# ir2104_V1_0.net
KiCad netlist of a schematic drawn in EasyEDA Pro
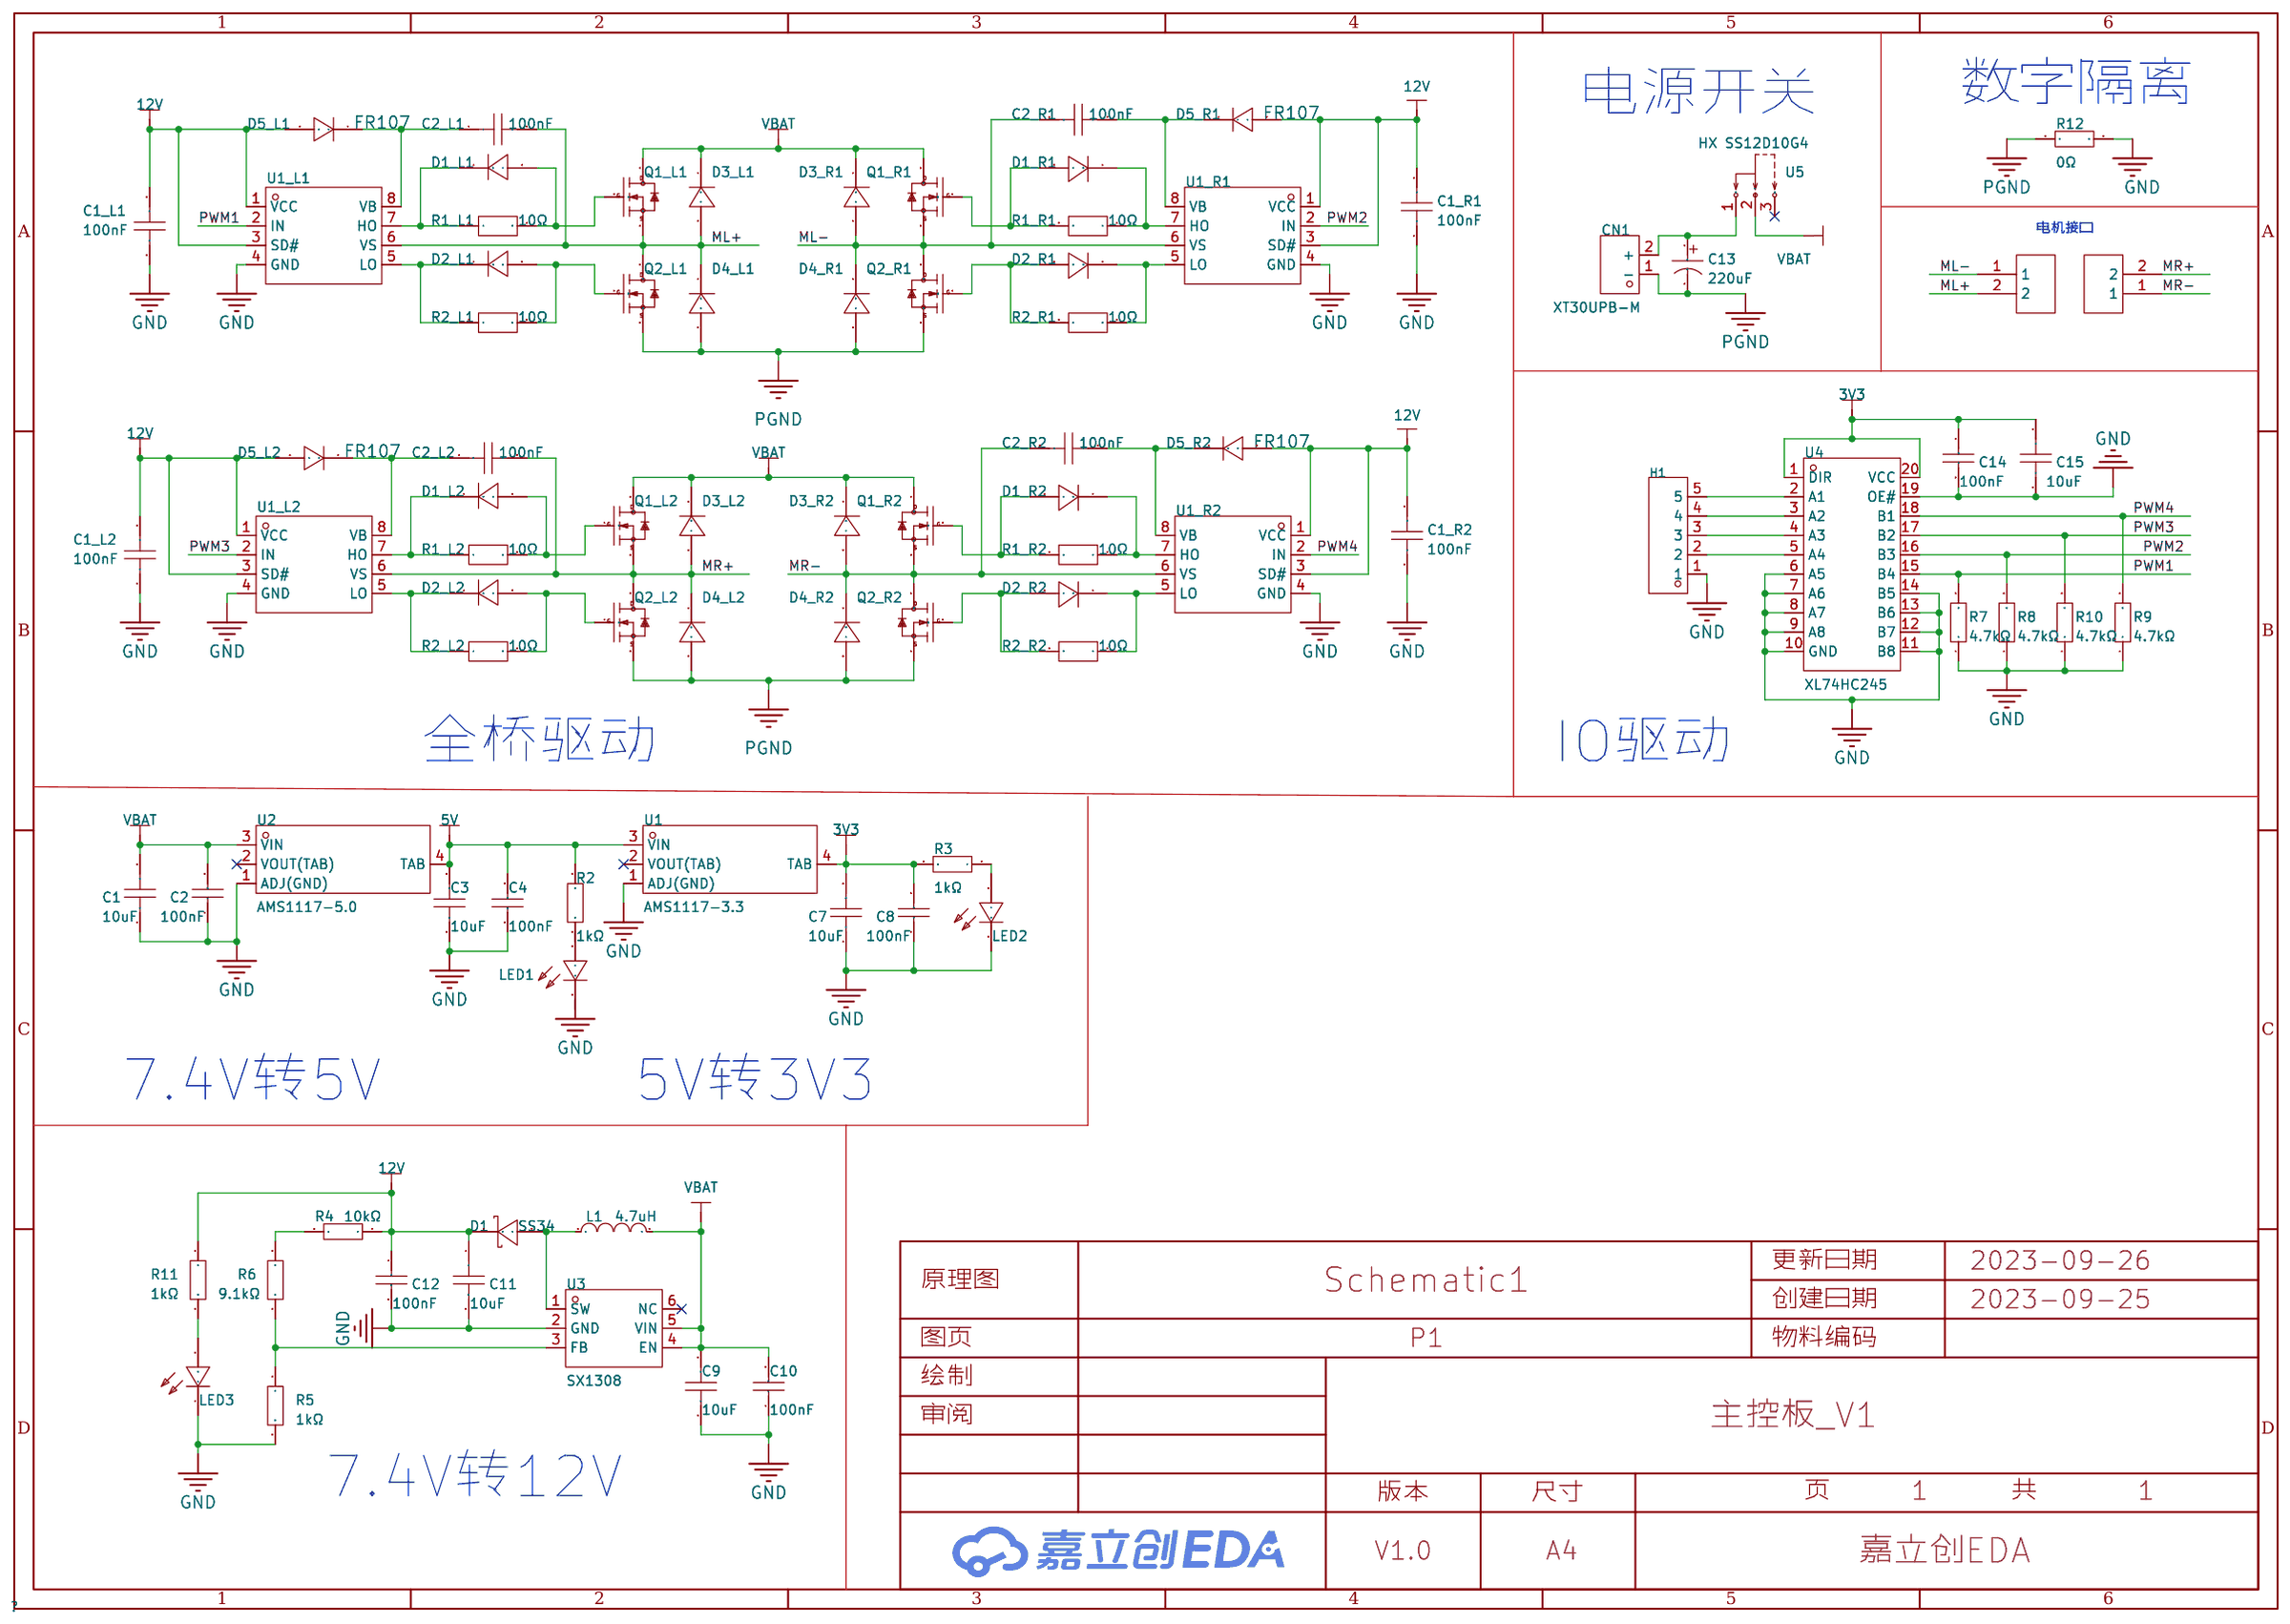
[diagram p0: schematic sheet]

(export (version "E")
  (design (tool "Eeschema 10.0.6"))
  (components
    (comp (ref "C1")
      (value "10uF")
      (footprint "easyedapro:C0603")
      (description "容值:10uF;精度:±20%;额定电压:25V;材质(温度系数):X5R;")
      (fields
        (field (name "Manufacturer Part") "CL10A106MA8NRNC")
        (field (name "Manufacturer") "SAMSUNG(三星)")
      )
      (libsource (lib "easyedapro") (part "CL10A106MA8NRNC"))
    )
    (comp (ref "C1_L1")
      (value "100nF")
      (footprint "easyedapro:C0603")
      (description "容值:100nF;精度:±10%;额定电压:50V;材质(温度系数):X7R;")
      (fields
        (field (name "Manufacturer Part") "CL10B104KB8NNNC")
        (field (name "Manufacturer") "SAMSUNG(三星)")
      )
      (libsource (lib "easyedapro") (part "CL10B104KB8NNNC"))
    )
    (comp (ref "C1_L2")
      (value "100nF")
      (footprint "easyedapro:C0603")
      (description "容值:100nF;精度:±10%;额定电压:50V;材质(温度系数):X7R;")
      (fields
        (field (name "Manufacturer Part") "CL10B104KB8NNNC")
        (field (name "Manufacturer") "SAMSUNG(三星)")
      )
      (libsource (lib "easyedapro") (part "CL10B104KB8NNNC"))
    )
    (comp (ref "C1_R1")
      (value "100nF")
      (footprint "easyedapro:C0603")
      (description "容值:100nF;精度:±10%;额定电压:50V;材质(温度系数):X7R;")
      (fields
        (field (name "Manufacturer Part") "CL10B104KB8NNNC")
        (field (name "Manufacturer") "SAMSUNG(三星)")
      )
      (libsource (lib "easyedapro") (part "CL10B104KB8NNNC"))
    )
    (comp (ref "C1_R2")
      (value "100nF")
      (footprint "easyedapro:C0603")
      (description "容值:100nF;精度:±10%;额定电压:50V;材质(温度系数):X7R;")
      (fields
        (field (name "Manufacturer Part") "CL10B104KB8NNNC")
        (field (name "Manufacturer") "SAMSUNG(三星)")
      )
      (libsource (lib "easyedapro") (part "CL10B104KB8NNNC"))
    )
    (comp (ref "C2")
      (value "100nF")
      (footprint "easyedapro:C0603")
      (description "容值:100nF;精度:±10%;额定电压:50V;材质(温度系数):X7R;")
      (fields (field (name "Manufacturer Part") "0603B104K500NT") (field (name "Manufacturer") "FH(风华)"))
      (libsource (lib "easyedapro") (part "0603B104K500NT"))
    )
    (comp (ref "C2_L1")
      (value "100nF")
      (footprint "easyedapro:C0603")
      (description "容值:100nF;精度:±10%;额定电压:50V;材质(温度系数):X7R;")
      (fields
        (field (name "Manufacturer Part") "CL10B104KB8NNNC")
        (field (name "Manufacturer") "SAMSUNG(三星)")
      )
      (libsource (lib "easyedapro") (part "CL10B104KB8NNNC"))
    )
    (comp (ref "C2_L2")
      (value "100nF")
      (footprint "easyedapro:C0603")
      (description "容值:100nF;精度:±10%;额定电压:50V;材质(温度系数):X7R;")
      (fields
        (field (name "Manufacturer Part") "CL10B104KB8NNNC")
        (field (name "Manufacturer") "SAMSUNG(三星)")
      )
      (libsource (lib "easyedapro") (part "CL10B104KB8NNNC"))
    )
    (comp (ref "C2_R1")
      (value "100nF")
      (footprint "easyedapro:C0603")
      (description "容值:100nF;精度:±10%;额定电压:50V;材质(温度系数):X7R;")
      (fields
        (field (name "Manufacturer Part") "CL10B104KB8NNNC")
        (field (name "Manufacturer") "SAMSUNG(三星)")
      )
      (libsource (lib "easyedapro") (part "CL10B104KB8NNNC"))
    )
    (comp (ref "C2_R2")
      (value "100nF")
      (footprint "easyedapro:C0603")
      (description "容值:100nF;精度:±10%;额定电压:50V;材质(温度系数):X7R;")
      (fields
        (field (name "Manufacturer Part") "CL10B104KB8NNNC")
        (field (name "Manufacturer") "SAMSUNG(三星)")
      )
      (libsource (lib "easyedapro") (part "CL10B104KB8NNNC"))
    )
    (comp (ref "C3")
      (value "10uF")
      (footprint "easyedapro:C0603")
      (description "容值:10uF;精度:±20%;额定电压:25V;材质(温度系数):X5R;")
      (fields
        (field (name "Manufacturer Part") "CL10A106MA8NRNC")
        (field (name "Manufacturer") "SAMSUNG(三星)")
      )
      (libsource (lib "easyedapro") (part "CL10A106MA8NRNC"))
    )
    (comp (ref "C4")
      (value "100nF")
      (footprint "easyedapro:C0603")
      (description "容值:100nF;精度:±10%;额定电压:50V;材质(温度系数):X7R;")
      (fields (field (name "Manufacturer Part") "0603B104K500NT") (field (name "Manufacturer") "FH(风华)"))
      (libsource (lib "easyedapro") (part "0603B104K500NT"))
    )
    (comp (ref "C7")
      (value "10uF")
      (footprint "easyedapro:C0603")
      (description "容值:10uF;精度:±20%;额定电压:25V;材质(温度系数):X5R;")
      (fields
        (field (name "Manufacturer Part") "CL10A106MA8NRNC")
        (field (name "Manufacturer") "SAMSUNG(三星)")
      )
      (libsource (lib "easyedapro") (part "CL10A106MA8NRNC"))
    )
    (comp (ref "C8")
      (value "100nF")
      (footprint "easyedapro:C0603")
      (description "容值:100nF;精度:±10%;额定电压:50V;材质(温度系数):X7R;")
      (fields (field (name "Manufacturer Part") "0603B104K500NT") (field (name "Manufacturer") "FH(风华)"))
      (libsource (lib "easyedapro") (part "0603B104K500NT"))
    )
    (comp (ref "C9")
      (value "10uF")
      (footprint "easyedapro:C0603")
      (description "容值:10uF;精度:±20%;额定电压:25V;材质(温度系数):X5R;")
      (fields
        (field (name "Manufacturer Part") "CL10A106MA8NRNC")
        (field (name "Manufacturer") "SAMSUNG(三星)")
      )
      (libsource (lib "easyedapro") (part "CL10A106MA8NRNC"))
    )
    (comp (ref "C10")
      (value "100nF")
      (footprint "easyedapro:C0603")
      (description "容值:100nF;精度:±10%;额定电压:50V;材质(温度系数):X7R;")
      (fields (field (name "Manufacturer Part") "0603B104K500NT") (field (name "Manufacturer") "FH(风华)"))
      (libsource (lib "easyedapro") (part "0603B104K500NT"))
    )
    (comp (ref "C11")
      (value "10uF")
      (footprint "easyedapro:C0603")
      (description "容值:10uF;精度:±20%;额定电压:25V;材质(温度系数):X5R;")
      (fields
        (field (name "Manufacturer Part") "CL10A106MA8NRNC")
        (field (name "Manufacturer") "SAMSUNG(三星)")
      )
      (libsource (lib "easyedapro") (part "CL10A106MA8NRNC"))
    )
    (comp (ref "C12")
      (value "100nF")
      (footprint "easyedapro:C0603")
      (description "容值:100nF;精度:±10%;额定电压:50V;材质(温度系数):X7R;")
      (fields (field (name "Manufacturer Part") "0603B104K500NT") (field (name "Manufacturer") "FH(风华)"))
      (libsource (lib "easyedapro") (part "0603B104K500NT"))
    )
    (comp (ref "C13")
      (value "220uF")
      (footprint "easyedapro:CAP-TH_BD8.0-P3.50-D0.6-FD")
      (description "容值:220uF;精度:±20%;额定电压:35V;纹波电流:-;等效串联电阻:-;")
      (fields
        (field (name "Manufacturer Part") "KM227M035F12RR0VH2FP0")
        (field (name "Manufacturer") "CX(承兴)")
      )
      (libsource (lib "easyedapro") (part "220uf/35V"))
    )
    (comp (ref "C14")
      (value "100nF")
      (footprint "easyedapro:C0603")
      (description "容值:100nF;精度:±10%;额定电压:50V;材质(温度系数):X7R;")
      (fields (field (name "Manufacturer Part") "0603B104K500NT") (field (name "Manufacturer") "FH(风华)"))
      (libsource (lib "easyedapro") (part "0603B104K500NT"))
    )
    (comp (ref "C15")
      (value "10uF")
      (footprint "easyedapro:C0603")
      (description "容值:10uF;精度:±20%;额定电压:25V;材质(温度系数):X5R;")
      (fields
        (field (name "Manufacturer Part") "CL10A106MA8NRNC")
        (field (name "Manufacturer") "SAMSUNG(三星)")
      )
      (libsource (lib "easyedapro") (part "CL10A106MA8NRNC"))
    )
    (comp (ref "CN1")
      (value "XT30UPB-M")
      (footprint "easyedapro:CONN-TH_XT30UPB-M")
      (fields (field (name "Manufacturer") "AMASS(艾迈斯)"))
      (libsource (lib "easyedapro") (part "XT30UPB-M"))
    )
    (comp (ref "D1")
      (value "SS34")
      (footprint "easyedapro:SMA_L4.3-W2.6-LS5.2-RD")
      (description "二极管配置:独立式;直流反向耐压(Vr):40V;平均整流电流(Io):3A;正向压降(Vf):550mV@3A;")
      (fields (field (name "Manufacturer") "MDD"))
      (libsource (lib "easyedapro") (part "SS34_C8678"))
    )
    (comp (ref "D1_L1")
      (value "US1M")
      (footprint "easyedapro:SMA_L4.4-W2.8-LS5.4-RD")
      (fields (field (name "Manufacturer") "MDD"))
      (libsource (lib "easyedapro") (part "US1MG_C412437"))
    )
    (comp (ref "D1_L2")
      (value "US1M")
      (footprint "easyedapro:SMA_L4.4-W2.8-LS5.4-RD")
      (fields (field (name "Manufacturer") "MDD"))
      (libsource (lib "easyedapro") (part "US1MG_C412437"))
    )
    (comp (ref "D1_R1")
      (value "US1M")
      (footprint "easyedapro:SMA_L4.4-W2.8-LS5.4-RD")
      (fields (field (name "Manufacturer") "MDD"))
      (libsource (lib "easyedapro") (part "US1MG_C412437"))
    )
    (comp (ref "D1_R2")
      (value "US1M")
      (footprint "easyedapro:SMA_L4.4-W2.8-LS5.4-RD")
      (fields (field (name "Manufacturer") "MDD"))
      (libsource (lib "easyedapro") (part "US1MG_C412437"))
    )
    (comp (ref "D2_L1")
      (value "US1M")
      (footprint "easyedapro:SMA_L4.4-W2.8-LS5.4-RD")
      (fields (field (name "Manufacturer") "MDD"))
      (libsource (lib "easyedapro") (part "US1MG_C412437"))
    )
    (comp (ref "D2_L2")
      (value "US1M")
      (footprint "easyedapro:SMA_L4.4-W2.8-LS5.4-RD")
      (fields (field (name "Manufacturer") "MDD"))
      (libsource (lib "easyedapro") (part "US1MG_C412437"))
    )
    (comp (ref "D2_R1")
      (value "US1M")
      (footprint "easyedapro:SMA_L4.4-W2.8-LS5.4-RD")
      (fields (field (name "Manufacturer") "MDD"))
      (libsource (lib "easyedapro") (part "US1MG_C412437"))
    )
    (comp (ref "D2_R2")
      (value "US1M")
      (footprint "easyedapro:SMA_L4.4-W2.8-LS5.4-RD")
      (fields (field (name "Manufacturer") "MDD"))
      (libsource (lib "easyedapro") (part "US1MG_C412437"))
    )
    (comp (ref "D3_L1")
      (value "US1M")
      (footprint "easyedapro:SMA_L4.4-W2.8-LS5.4-RD")
      (fields (field (name "Manufacturer") "MDD"))
      (libsource (lib "easyedapro") (part "US1MG_C412437"))
    )
    (comp (ref "D3_L2")
      (value "US1M")
      (footprint "easyedapro:SMA_L4.4-W2.8-LS5.4-RD")
      (fields (field (name "Manufacturer") "MDD"))
      (libsource (lib "easyedapro") (part "US1MG_C412437"))
    )
    (comp (ref "D3_R1")
      (value "US1M")
      (footprint "easyedapro:SMA_L4.4-W2.8-LS5.4-RD")
      (fields (field (name "Manufacturer") "MDD"))
      (libsource (lib "easyedapro") (part "US1MG_C412437"))
    )
    (comp (ref "D3_R2")
      (value "US1M")
      (footprint "easyedapro:SMA_L4.4-W2.8-LS5.4-RD")
      (fields (field (name "Manufacturer") "MDD"))
      (libsource (lib "easyedapro") (part "US1MG_C412437"))
    )
    (comp (ref "D4_L1")
      (value "US1M")
      (footprint "easyedapro:SMA_L4.4-W2.8-LS5.4-RD")
      (fields (field (name "Manufacturer") "MDD"))
      (libsource (lib "easyedapro") (part "US1MG_C412437"))
    )
    (comp (ref "D4_L2")
      (value "US1M")
      (footprint "easyedapro:SMA_L4.4-W2.8-LS5.4-RD")
      (fields (field (name "Manufacturer") "MDD"))
      (libsource (lib "easyedapro") (part "US1MG_C412437"))
    )
    (comp (ref "D4_R1")
      (value "US1M")
      (footprint "easyedapro:SMA_L4.4-W2.8-LS5.4-RD")
      (fields (field (name "Manufacturer") "MDD"))
      (libsource (lib "easyedapro") (part "US1MG_C412437"))
    )
    (comp (ref "D4_R2")
      (value "US1M")
      (footprint "easyedapro:SMA_L4.4-W2.8-LS5.4-RD")
      (fields (field (name "Manufacturer") "MDD"))
      (libsource (lib "easyedapro") (part "US1MG_C412437"))
    )
    (comp (ref "D5_L1")
      (value "FR107")
      (footprint "easyedapro:SOD-123_L2.8-W1.8-LS3.7-RD")
      (fields (field (name "Manufacturer") "BORN(伯恩半导体)"))
      (libsource (lib "easyedapro") (part "FR107_C511885"))
    )
    (comp (ref "D5_L2")
      (value "FR107")
      (footprint "easyedapro:SOD-123_L2.8-W1.8-LS3.7-RD")
      (fields (field (name "Manufacturer") "BORN(伯恩半导体)"))
      (libsource (lib "easyedapro") (part "FR107_C511885"))
    )
    (comp (ref "D5_R1")
      (value "FR107")
      (footprint "easyedapro:SOD-123_L2.8-W1.8-LS3.7-RD")
      (fields (field (name "Manufacturer") "BORN(伯恩半导体)"))
      (libsource (lib "easyedapro") (part "FR107_C511885"))
    )
    (comp (ref "D5_R2")
      (value "FR107")
      (footprint "easyedapro:SOD-123_L2.8-W1.8-LS3.7-RD")
      (fields (field (name "Manufacturer") "BORN(伯恩半导体)"))
      (libsource (lib "easyedapro") (part "FR107_C511885"))
    )
    (comp (ref "H1")
      (value "PZ254V-11-05P")
      (footprint "easyedapro:HDR-TH_5P-P2.54-V-M")
      (fields (field (name "Manufacturer") "XFCN(兴飞)"))
      (libsource (lib "easyedapro") (part "PZ254V-11-05P"))
    )
    (comp (ref "L1")
      (value "4.7uH")
      (footprint "easyedapro:IND-SMD_L5.4-W5.2_FXL0530")
      (description "电感值:4.7uH;精度:±20%;额定电流:4.5A;饱和电流(Isat):5A;")
      (fields (field (name "Manufacturer Part") "FXL0530-4R7-M") (field (name "Manufacturer") "cjiang(长江微电)"))
      (libsource (lib "easyedapro") (part "FXL0530-4R7-M"))
    )
    (comp (ref "LED1")
      (value "NCD0603R1")
      (footprint "easyedapro:LED0603-RD_RED")
      (description "发光颜色:红灯;")
      (fields (field (name "Manufacturer") "国星光电"))
      (libsource (lib "easyedapro") (part "FC-DA1608HRK-620D"))
    )
    (comp (ref "LED2")
      (value "NCD0603R1")
      (footprint "easyedapro:LED0603-RD_RED")
      (description "发光颜色:红灯;")
      (fields (field (name "Manufacturer") "国星光电"))
      (libsource (lib "easyedapro") (part "FC-DA1608HRK-620D"))
    )
    (comp (ref "LED3")
      (value "NCD0603R1")
      (footprint "easyedapro:LED0603-RD_RED")
      (description "发光颜色:红灯;")
      (fields (field (name "Manufacturer") "国星光电"))
      (libsource (lib "easyedapro") (part "FC-DA1608HRK-620D"))
    )
    (comp (ref "P1")
      (value "WJ500V-5.08-2P")
      (footprint "easyedapro:CONN-TH_2P-P5.00_WJ500V-5.08-2P")
      (fields (field (name "Manufacturer") "KANGNEX(康奈克斯电气)"))
      (libsource (lib "easyedapro") (part "WJ500V-5.08-2P-14-00A"))
    )
    (comp (ref "P2")
      (value "WJ500V-5.08-2P")
      (footprint "easyedapro:CONN-TH_2P-P5.00_WJ500V-5.08-2P")
      (fields (field (name "Manufacturer") "KANGNEX(康奈克斯电气)"))
      (libsource (lib "easyedapro") (part "WJ500V-5.08-2P-14-00A"))
    )
    (comp (ref "Q1_L1")
      (value "IRFR3607TRPBF")
      (footprint "easyedapro:TO-252-3_L6.5-W5.8-P4.58-BL")
      (fields (field (name "Manufacturer") "Infineon(英飞凌)"))
      (libsource (lib "easyedapro") (part "IRFR3607TRPBF"))
    )
    (comp (ref "Q1_L2")
      (value "IRFR3607TRPBF")
      (footprint "easyedapro:TO-252-3_L6.5-W5.8-P4.58-BL")
      (fields (field (name "Manufacturer") "Infineon(英飞凌)"))
      (libsource (lib "easyedapro") (part "IRFR3607TRPBF"))
    )
    (comp (ref "Q1_R1")
      (value "IRFR3607TRPBF")
      (footprint "easyedapro:TO-252-3_L6.5-W5.8-P4.58-BL")
      (fields (field (name "Manufacturer") "Infineon(英飞凌)"))
      (libsource (lib "easyedapro") (part "IRFR3607TRPBF"))
    )
    (comp (ref "Q1_R2")
      (value "IRFR3607TRPBF")
      (footprint "easyedapro:TO-252-3_L6.5-W5.8-P4.58-BL")
      (fields (field (name "Manufacturer") "Infineon(英飞凌)"))
      (libsource (lib "easyedapro") (part "IRFR3607TRPBF"))
    )
    (comp (ref "Q2_L1")
      (value "IRFR3607TRPBF")
      (footprint "easyedapro:TO-252-3_L6.5-W5.8-P4.58-BL")
      (fields (field (name "Manufacturer") "Infineon(英飞凌)"))
      (libsource (lib "easyedapro") (part "IRFR3607TRPBF"))
    )
    (comp (ref "Q2_L2")
      (value "IRFR3607TRPBF")
      (footprint "easyedapro:TO-252-3_L6.5-W5.8-P4.58-BL")
      (fields (field (name "Manufacturer") "Infineon(英飞凌)"))
      (libsource (lib "easyedapro") (part "IRFR3607TRPBF"))
    )
    (comp (ref "Q2_R1")
      (value "IRFR3607TRPBF")
      (footprint "easyedapro:TO-252-3_L6.5-W5.8-P4.58-BL")
      (fields (field (name "Manufacturer") "Infineon(英飞凌)"))
      (libsource (lib "easyedapro") (part "IRFR3607TRPBF"))
    )
    (comp (ref "Q2_R2")
      (value "IRFR3607TRPBF")
      (footprint "easyedapro:TO-252-3_L6.5-W5.8-P4.58-BL")
      (fields (field (name "Manufacturer") "Infineon(英飞凌)"))
      (libsource (lib "easyedapro") (part "IRFR3607TRPBF"))
    )
    (comp (ref "R1_L1")
      (value "10Ω")
      (footprint "easyedapro:R0603")
      (description "阻值:10Ω;精度:±0.5%;功率:250mW;")
      (fields (field (name "Manufacturer Part") "ERJUP3D10R0V") (field (name "Manufacturer") "PANASONIC(松下)"))
      (libsource (lib "easyedapro") (part "ERJUP3D10R0V"))
    )
    (comp (ref "R1_L2")
      (value "10Ω")
      (footprint "easyedapro:R0603")
      (description "阻值:10Ω;精度:±0.5%;功率:250mW;")
      (fields (field (name "Manufacturer Part") "ERJUP3D10R0V") (field (name "Manufacturer") "PANASONIC(松下)"))
      (libsource (lib "easyedapro") (part "ERJUP3D10R0V"))
    )
    (comp (ref "R1_R1")
      (value "10Ω")
      (footprint "easyedapro:R0603")
      (description "阻值:10Ω;精度:±0.5%;功率:250mW;")
      (fields (field (name "Manufacturer Part") "ERJUP3D10R0V") (field (name "Manufacturer") "PANASONIC(松下)"))
      (libsource (lib "easyedapro") (part "ERJUP3D10R0V"))
    )
    (comp (ref "R1_R2")
      (value "10Ω")
      (footprint "easyedapro:R0603")
      (description "阻值:10Ω;精度:±0.5%;功率:250mW;")
      (fields (field (name "Manufacturer Part") "ERJUP3D10R0V") (field (name "Manufacturer") "PANASONIC(松下)"))
      (libsource (lib "easyedapro") (part "ERJUP3D10R0V"))
    )
    (comp (ref "R2")
      (value "1kΩ")
      (footprint "easyedapro:R0603")
      (description "电阻类型:厚膜电阻;阻值:1kΩ;精度:±1%;功率:100mW;")
      (fields
        (field (name "Manufacturer Part") "0603WAF1001T5E")
        (field (name "Manufacturer") "UNI-ROYAL(厚声)")
      )
      (libsource (lib "easyedapro") (part "0603WAF1001T5E"))
    )
    (comp (ref "R2_L1")
      (value "10Ω")
      (footprint "easyedapro:R0603")
      (description "阻值:10Ω;精度:±0.5%;功率:250mW;")
      (fields (field (name "Manufacturer Part") "ERJUP3D10R0V") (field (name "Manufacturer") "PANASONIC(松下)"))
      (libsource (lib "easyedapro") (part "ERJUP3D10R0V"))
    )
    (comp (ref "R2_L2")
      (value "10Ω")
      (footprint "easyedapro:R0603")
      (description "阻值:10Ω;精度:±0.5%;功率:250mW;")
      (fields (field (name "Manufacturer Part") "ERJUP3D10R0V") (field (name "Manufacturer") "PANASONIC(松下)"))
      (libsource (lib "easyedapro") (part "ERJUP3D10R0V"))
    )
    (comp (ref "R2_R1")
      (value "10Ω")
      (footprint "easyedapro:R0603")
      (description "阻值:10Ω;精度:±0.5%;功率:250mW;")
      (fields (field (name "Manufacturer Part") "ERJUP3D10R0V") (field (name "Manufacturer") "PANASONIC(松下)"))
      (libsource (lib "easyedapro") (part "ERJUP3D10R0V"))
    )
    (comp (ref "R2_R2")
      (value "10Ω")
      (footprint "easyedapro:R0603")
      (description "阻值:10Ω;精度:±0.5%;功率:250mW;")
      (fields (field (name "Manufacturer Part") "ERJUP3D10R0V") (field (name "Manufacturer") "PANASONIC(松下)"))
      (libsource (lib "easyedapro") (part "ERJUP3D10R0V"))
    )
    (comp (ref "R3")
      (value "1kΩ")
      (footprint "easyedapro:R0603")
      (description "电阻类型:厚膜电阻;阻值:1kΩ;精度:±1%;功率:100mW;")
      (fields
        (field (name "Manufacturer Part") "0603WAF1001T5E")
        (field (name "Manufacturer") "UNI-ROYAL(厚声)")
      )
      (libsource (lib "easyedapro") (part "0603WAF1001T5E"))
    )
    (comp (ref "R4")
      (value "10kΩ")
      (footprint "easyedapro:R0603")
      (description "电阻类型:薄膜电阻;阻值:10kΩ;精度:±0.1%;功率:100mW;")
      (fields (field (name "Manufacturer Part") "RT0603BRD0710KL") (field (name "Manufacturer") "YAGEO(国巨)"))
      (libsource (lib "easyedapro") (part "RT0603BRD0710KL"))
    )
    (comp (ref "R5")
      (value "1kΩ")
      (footprint "easyedapro:R0603")
      (description "电阻类型:薄膜电阻;阻值:1kΩ;精度:±0.1%;功率:100mW;")
      (fields (field (name "Manufacturer Part") "RT0603BRD071KL") (field (name "Manufacturer") "YAGEO(国巨)"))
      (libsource (lib "easyedapro") (part "RT0603BRD071KL"))
    )
    (comp (ref "R6")
      (value "9.1kΩ")
      (footprint "easyedapro:R0603")
      (description "电阻类型:薄膜电阻;阻值:9.1kΩ;精度:±0.1%;功率:100mW;")
      (fields (field (name "Manufacturer Part") "PTFR0603B9K10P9") (field (name "Manufacturer") "RESI(开步睿思）"))
      (libsource (lib "easyedapro") (part "PTFR0603B9K10P9"))
    )
    (comp (ref "R7")
      (value "4.7kΩ")
      (footprint "easyedapro:R0603")
      (description "电阻类型:厚膜电阻;阻值:4.7kΩ;精度:±1%;功率:100mW;")
      (fields
        (field (name "Manufacturer Part") "0603WAF4701T5E")
        (field (name "Manufacturer") "UNI-ROYAL(厚声)")
      )
      (libsource (lib "easyedapro") (part "0603WAF4701T5E"))
    )
    (comp (ref "R8")
      (value "4.7kΩ")
      (footprint "easyedapro:R0603")
      (description "电阻类型:厚膜电阻;阻值:4.7kΩ;精度:±1%;功率:100mW;")
      (fields
        (field (name "Manufacturer Part") "0603WAF4701T5E")
        (field (name "Manufacturer") "UNI-ROYAL(厚声)")
      )
      (libsource (lib "easyedapro") (part "0603WAF4701T5E"))
    )
    (comp (ref "R9")
      (value "4.7kΩ")
      (footprint "easyedapro:R0603")
      (description "电阻类型:厚膜电阻;阻值:4.7kΩ;精度:±1%;功率:100mW;")
      (fields
        (field (name "Manufacturer Part") "0603WAF4701T5E")
        (field (name "Manufacturer") "UNI-ROYAL(厚声)")
      )
      (libsource (lib "easyedapro") (part "0603WAF4701T5E"))
    )
    (comp (ref "R10")
      (value "4.7kΩ")
      (footprint "easyedapro:R0603")
      (description "电阻类型:厚膜电阻;阻值:4.7kΩ;精度:±1%;功率:100mW;")
      (fields
        (field (name "Manufacturer Part") "0603WAF4701T5E")
        (field (name "Manufacturer") "UNI-ROYAL(厚声)")
      )
      (libsource (lib "easyedapro") (part "0603WAF4701T5E"))
    )
    (comp (ref "R11")
      (value "1kΩ")
      (footprint "easyedapro:R0603")
      (description "电阻类型:厚膜电阻;阻值:1kΩ;精度:±1%;功率:100mW;")
      (fields
        (field (name "Manufacturer Part") "0603WAF1001T5E")
        (field (name "Manufacturer") "UNI-ROYAL(厚声)")
      )
      (libsource (lib "easyedapro") (part "0603WAF1001T5E"))
    )
    (comp (ref "R12")
      (value "0Ω")
      (footprint "easyedapro:R0805")
      (description "电阻类型:厚膜电阻;阻值:0Ω;精度:±1%;功率:125mW;")
      (fields
        (field (name "Manufacturer Part") "0805W8F0000T5E")
        (field (name "Manufacturer") "UNI-ROYAL(厚声)")
      )
      (libsource (lib "easyedapro") (part "0805W8F0000T5E"))
    )
    (comp (ref "U1")
      (value "AMS1117-3.3")
      (footprint "easyedapro:SOT-223-4_L6.5-W3.5-P2.30-LS7.0-BR")
      (description "输出类型:固定;输出极性:正;最大输入电压:18V;输出电压:3.3V;输出电流:1A;电源纹波抑制比(PSRR):60dB@(120Hz);")
      (fields (field (name "Manufacturer") "UMW(广东友台半导体)"))
      (libsource (lib "easyedapro") (part "AMS1117-3.3_C347222"))
    )
    (comp (ref "U1_L1")
      (value "EG2104")
      (footprint "easyedapro:SOP-8_L5.0-W4.0-P1.27-LS6.2-BL")
      (description "高性价比, 600V，半桥式Nmos预驱动器")
      (fields (field (name "Manufacturer") "EG(屹晶微)"))
      (libsource (lib "easyedapro") (part "EG2104"))
    )
    (comp (ref "U1_L2")
      (value "EG2104")
      (footprint "easyedapro:SOP-8_L5.0-W4.0-P1.27-LS6.2-BL")
      (description "高性价比, 600V，半桥式Nmos预驱动器")
      (fields (field (name "Manufacturer") "EG(屹晶微)"))
      (libsource (lib "easyedapro") (part "EG2104"))
    )
    (comp (ref "U1_R1")
      (value "EG2104")
      (footprint "easyedapro:SOP-8_L5.0-W4.0-P1.27-LS6.2-BL")
      (description "高性价比, 600V，半桥式Nmos预驱动器")
      (fields (field (name "Manufacturer") "EG(屹晶微)"))
      (libsource (lib "easyedapro") (part "EG2104"))
    )
    (comp (ref "U1_R2")
      (value "EG2104")
      (footprint "easyedapro:SOP-8_L5.0-W4.0-P1.27-LS6.2-BL")
      (description "高性价比, 600V，半桥式Nmos预驱动器")
      (fields (field (name "Manufacturer") "EG(屹晶微)"))
      (libsource (lib "easyedapro") (part "EG2104"))
    )
    (comp (ref "U2")
      (value "AMS1117-5.0")
      (footprint "easyedapro:SOT-223_L6.7-W3.5-P2.30-BR")
      (description "输出类型:固定;输出极性:正;最大输入电压:18V;输出电压:5V;输出电流:1A;电源纹波抑制比(PSRR):60dB@(120Hz);")
      (fields (field (name "Manufacturer") "UMW(广东友台半导体)"))
      (libsource (lib "easyedapro") (part "AMS1117-5.0_C347223"))
    )
    (comp (ref "U3")
      (value "SX1308")
      (footprint "easyedapro:SOT-23-6_L2.9-W1.6-P0.95-LS2.8-BL")
      (description "功能类型:升压型;同步整流:否;输出通道数:1;拓扑结构:升压式;输入电压:2V~24V;输出电压:28V;输出电流(最大值):-;开关频率:1.2MHz;")
      (fields (field (name "Manufacturer") "SX(硕芯科技)"))
      (libsource (lib "easyedapro") (part "SX1308"))
    )
    (comp (ref "U4")
      (value "XL74HC245")
      (footprint "easyedapro:SOP-20_L12.8-W7.5-P1.27-LS10.4-BL")
      (description "八路总线收发器")
      (fields (field (name "Manufacturer") "XINLUDA(信路达)"))
      (libsource (lib "easyedapro") (part "XL74HC245"))
    )
    (comp (ref "U5")
      (value "HX SS12D10G4")
      (footprint "easyedapro:SW-TH_SHOU-HAN_SS12D10G4")
      (fields (field (name "Manufacturer") "hanxia(韩下)"))
      (libsource (lib "easyedapro") (part "HX SS12D10G4"))
    )
  )
  (nets
    (net (code "1") (name "/ML+") (class "Default")
      (node (ref "C2_L1") (pin "2") (pinfunction "2_2") (pintype "input"))
      (node (ref "D3_L1") (pin "2") (pinfunction "A_2") (pintype "input"))
      (node (ref "D4_L1") (pin "1") (pinfunction "C_1") (pintype "input"))
      (node (ref "P1") (pin "2") (pinfunction "2_2") (pintype "input"))
      (node (ref "Q1_L1") (pin "3") (pinfunction "S_3") (pintype "input"))
      (node (ref "Q2_L1") (pin "2") (pinfunction "D_2") (pintype "input"))
      (node (ref "U1_L1") (pin "6") (pinfunction "VS_6") (pintype "input"))
    )
    (net (code "2") (name "/ML-") (class "Default")
      (node (ref "C2_R1") (pin "2") (pinfunction "2_2") (pintype "input"))
      (node (ref "D3_R1") (pin "2") (pinfunction "A_2") (pintype "input"))
      (node (ref "D4_R1") (pin "1") (pinfunction "C_1") (pintype "input"))
      (node (ref "P1") (pin "1") (pinfunction "1_1") (pintype "input"))
      (node (ref "Q1_R1") (pin "3") (pinfunction "S_3") (pintype "input"))
      (node (ref "Q2_R1") (pin "2") (pinfunction "D_2") (pintype "input"))
      (node (ref "U1_R1") (pin "6") (pinfunction "VS_6") (pintype "input"))
    )
    (net (code "3") (name "/MR+") (class "Default")
      (node (ref "C2_L2") (pin "2") (pinfunction "2_2") (pintype "input"))
      (node (ref "D3_L2") (pin "2") (pinfunction "A_2") (pintype "input"))
      (node (ref "D4_L2") (pin "1") (pinfunction "C_1") (pintype "input"))
      (node (ref "P2") (pin "2") (pinfunction "2_2") (pintype "input"))
      (node (ref "Q1_L2") (pin "3") (pinfunction "S_3") (pintype "input"))
      (node (ref "Q2_L2") (pin "2") (pinfunction "D_2") (pintype "input"))
      (node (ref "U1_L2") (pin "6") (pinfunction "VS_6") (pintype "input"))
    )
    (net (code "4") (name "/MR-") (class "Default")
      (node (ref "C2_R2") (pin "2") (pinfunction "2_2") (pintype "input"))
      (node (ref "D3_R2") (pin "2") (pinfunction "A_2") (pintype "input"))
      (node (ref "D4_R2") (pin "1") (pinfunction "C_1") (pintype "input"))
      (node (ref "P2") (pin "1") (pinfunction "1_1") (pintype "input"))
      (node (ref "Q1_R2") (pin "3") (pinfunction "S_3") (pintype "input"))
      (node (ref "Q2_R2") (pin "2") (pinfunction "D_2") (pintype "input"))
      (node (ref "U1_R2") (pin "6") (pinfunction "VS_6") (pintype "input"))
    )
    (net (code "5") (name "/PWM1") (class "Default")
      (node (ref "R7") (pin "2") (pinfunction "2_2") (pintype "input"))
      (node (ref "U1_L1") (pin "2") (pinfunction "IN_2") (pintype "input"))
      (node (ref "U4") (pin "15") (pinfunction "B4_15") (pintype "input"))
    )
    (net (code "6") (name "/PWM2") (class "Default")
      (node (ref "R8") (pin "2") (pinfunction "2_2") (pintype "input"))
      (node (ref "U1_R1") (pin "2") (pinfunction "IN_2") (pintype "input"))
      (node (ref "U4") (pin "16") (pinfunction "B3_16") (pintype "input"))
    )
    (net (code "7") (name "/PWM3") (class "Default")
      (node (ref "R10") (pin "2") (pinfunction "2_2") (pintype "input"))
      (node (ref "U1_L2") (pin "2") (pinfunction "IN_2") (pintype "input"))
      (node (ref "U4") (pin "17") (pinfunction "B2_17") (pintype "input"))
    )
    (net (code "8") (name "/PWM4") (class "Default")
      (node (ref "R9") (pin "2") (pinfunction "2_2") (pintype "input"))
      (node (ref "U1_R2") (pin "2") (pinfunction "IN_2") (pintype "input"))
      (node (ref "U4") (pin "18") (pinfunction "B1_18") (pintype "input"))
    )
    (net (code "9") (name "3V3") (class "Default")
      (node (ref "C14") (pin "1") (pinfunction "1_1") (pintype "input"))
      (node (ref "C15") (pin "1") (pinfunction "1_1") (pintype "input"))
      (node (ref "C7") (pin "2") (pinfunction "2_2") (pintype "input"))
      (node (ref "C8") (pin "2") (pinfunction "2_2") (pintype "input"))
      (node (ref "R3") (pin "2") (pinfunction "2_2") (pintype "input"))
      (node (ref "U1") (pin "4") (pinfunction "TAB_4") (pintype "input"))
      (node (ref "U4") (pin "1") (pinfunction "DIR_1") (pintype "input"))
      (node (ref "U4") (pin "20") (pinfunction "VCC_20") (pintype "input"))
    )
    (net (code "10") (name "5V") (class "Default")
      (node (ref "C3") (pin "2") (pinfunction "2_2") (pintype "input"))
      (node (ref "C4") (pin "2") (pinfunction "2_2") (pintype "input"))
      (node (ref "R2") (pin "1") (pinfunction "1_1") (pintype "input"))
      (node (ref "U1") (pin "3") (pinfunction "VIN_3") (pintype "input"))
      (node (ref "U2") (pin "4") (pinfunction "TAB_4") (pintype "input"))
    )
    (net (code "11") (name "12V") (class "Default")
      (node (ref "C11") (pin "1") (pinfunction "1_1") (pintype "input"))
      (node (ref "C12") (pin "1") (pinfunction "1_1") (pintype "input"))
      (node (ref "C1_L1") (pin "2") (pinfunction "2_2") (pintype "input"))
      (node (ref "C1_L2") (pin "2") (pinfunction "2_2") (pintype "input"))
      (node (ref "C1_R1") (pin "2") (pinfunction "2_2") (pintype "input"))
      (node (ref "C1_R2") (pin "2") (pinfunction "2_2") (pintype "input"))
      (node (ref "D1") (pin "1") (pinfunction "K_1") (pintype "input"))
      (node (ref "D5_L1") (pin "2") (pinfunction "A_2") (pintype "input"))
      (node (ref "D5_L2") (pin "2") (pinfunction "A_2") (pintype "input"))
      (node (ref "D5_R1") (pin "2") (pinfunction "A_2") (pintype "input"))
      (node (ref "D5_R2") (pin "2") (pinfunction "A_2") (pintype "input"))
      (node (ref "R11") (pin "1") (pinfunction "1_1") (pintype "input"))
      (node (ref "R4") (pin "1") (pinfunction "1_1") (pintype "input"))
      (node (ref "U1_L1") (pin "1") (pinfunction "VCC_1") (pintype "input"))
      (node (ref "U1_L1") (pin "3") (pinfunction "SD#_3") (pintype "input"))
      (node (ref "U1_L2") (pin "1") (pinfunction "VCC_1") (pintype "input"))
      (node (ref "U1_L2") (pin "3") (pinfunction "SD#_3") (pintype "input"))
      (node (ref "U1_R1") (pin "1") (pinfunction "VCC_1") (pintype "input"))
      (node (ref "U1_R1") (pin "3") (pinfunction "SD#_3") (pintype "input"))
      (node (ref "U1_R2") (pin "1") (pinfunction "VCC_1") (pintype "input"))
      (node (ref "U1_R2") (pin "3") (pinfunction "SD#_3") (pintype "input"))
    )
    (net (code "12") (name "GND") (class "Default")
      (node (ref "C1") (pin "1") (pinfunction "1_1") (pintype "input"))
      (node (ref "C10") (pin "1") (pinfunction "1_1") (pintype "input"))
      (node (ref "C11") (pin "2") (pinfunction "2_2") (pintype "input"))
      (node (ref "C12") (pin "2") (pinfunction "2_2") (pintype "input"))
      (node (ref "C14") (pin "2") (pinfunction "2_2") (pintype "input"))
      (node (ref "C15") (pin "2") (pinfunction "2_2") (pintype "input"))
      (node (ref "C1_L1") (pin "1") (pinfunction "1_1") (pintype "input"))
      (node (ref "C1_L2") (pin "1") (pinfunction "1_1") (pintype "input"))
      (node (ref "C1_R1") (pin "1") (pinfunction "1_1") (pintype "input"))
      (node (ref "C1_R2") (pin "1") (pinfunction "1_1") (pintype "input"))
      (node (ref "C2") (pin "1") (pinfunction "1_1") (pintype "input"))
      (node (ref "C3") (pin "1") (pinfunction "1_1") (pintype "input"))
      (node (ref "C4") (pin "1") (pinfunction "1_1") (pintype "input"))
      (node (ref "C7") (pin "1") (pinfunction "1_1") (pintype "input"))
      (node (ref "C8") (pin "1") (pinfunction "1_1") (pintype "input"))
      (node (ref "C9") (pin "1") (pinfunction "1_1") (pintype "input"))
      (node (ref "H1") (pin "1") (pinfunction "1_1") (pintype "input"))
      (node (ref "LED1") (pin "1") (pinfunction "K_1") (pintype "input"))
      (node (ref "LED2") (pin "1") (pinfunction "K_1") (pintype "input"))
      (node (ref "LED3") (pin "1") (pinfunction "K_1") (pintype "input"))
      (node (ref "R10") (pin "1") (pinfunction "1_1") (pintype "input"))
      (node (ref "R12") (pin "2") (pinfunction "2_2") (pintype "input"))
      (node (ref "R5") (pin "2") (pinfunction "2_2") (pintype "input"))
      (node (ref "R7") (pin "1") (pinfunction "1_1") (pintype "input"))
      (node (ref "R8") (pin "1") (pinfunction "1_1") (pintype "input"))
      (node (ref "R9") (pin "1") (pinfunction "1_1") (pintype "input"))
      (node (ref "U1") (pin "1") (pinfunction "ADJ(GND)_1") (pintype "input"))
      (node (ref "U1_L1") (pin "4") (pinfunction "GND_4") (pintype "input"))
      (node (ref "U1_L2") (pin "4") (pinfunction "GND_4") (pintype "input"))
      (node (ref "U1_R1") (pin "4") (pinfunction "GND_4") (pintype "input"))
      (node (ref "U1_R2") (pin "4") (pinfunction "GND_4") (pintype "input"))
      (node (ref "U2") (pin "1") (pinfunction "ADJ(GND)_1") (pintype "input"))
      (node (ref "U3") (pin "2") (pinfunction "GND_2") (pintype "input"))
      (node (ref "U4") (pin "10") (pinfunction "GND_10") (pintype "input"))
      (node (ref "U4") (pin "11") (pinfunction "B8_11") (pintype "input"))
      (node (ref "U4") (pin "12") (pinfunction "B7_12") (pintype "input"))
      (node (ref "U4") (pin "13") (pinfunction "B6_13") (pintype "input"))
      (node (ref "U4") (pin "14") (pinfunction "B5_14") (pintype "input"))
      (node (ref "U4") (pin "19") (pinfunction "OE#_19") (pintype "input"))
      (node (ref "U4") (pin "6") (pinfunction "A5_6") (pintype "input"))
      (node (ref "U4") (pin "7") (pinfunction "A6_7") (pintype "input"))
      (node (ref "U4") (pin "8") (pinfunction "A7_8") (pintype "input"))
      (node (ref "U4") (pin "9") (pinfunction "A8_9") (pintype "input"))
    )
    (net (code "13") (name "Net-(CN1-+)") (class "Default")
      (node (ref "C13") (pin "1") (pinfunction "1_1") (pintype "input"))
      (node (ref "CN1") (pin "2") (pinfunction "+_2") (pintype "input"))
      (node (ref "U5") (pin "1") (pinfunction "1_1") (pintype "input"))
    )
    (net (code "14") (name "Net-(D1-A)") (class "Default")
      (node (ref "D1") (pin "2") (pinfunction "A_2") (pintype "input"))
      (node (ref "L1") (pin "1") (pinfunction "1_1") (pintype "input"))
      (node (ref "U3") (pin "1") (pinfunction "SW_1") (pintype "input"))
    )
    (net (code "15") (name "Net-(D1_L1-A)") (class "Default")
      (node (ref "D1_L1") (pin "2") (pinfunction "A_2") (pintype "input"))
      (node (ref "Q1_L1") (pin "1") (pinfunction "G_1") (pintype "input"))
      (node (ref "R1_L1") (pin "2") (pinfunction "2_2") (pintype "input"))
    )
    (net (code "16") (name "Net-(D1_L1-C)") (class "Default")
      (node (ref "D1_L1") (pin "1") (pinfunction "C_1") (pintype "input"))
      (node (ref "R1_L1") (pin "1") (pinfunction "1_1") (pintype "input"))
      (node (ref "U1_L1") (pin "7") (pinfunction "HO_7") (pintype "input"))
    )
    (net (code "17") (name "Net-(D1_L2-A)") (class "Default")
      (node (ref "D1_L2") (pin "2") (pinfunction "A_2") (pintype "input"))
      (node (ref "Q1_L2") (pin "1") (pinfunction "G_1") (pintype "input"))
      (node (ref "R1_L2") (pin "2") (pinfunction "2_2") (pintype "input"))
    )
    (net (code "18") (name "Net-(D1_L2-C)") (class "Default")
      (node (ref "D1_L2") (pin "1") (pinfunction "C_1") (pintype "input"))
      (node (ref "R1_L2") (pin "1") (pinfunction "1_1") (pintype "input"))
      (node (ref "U1_L2") (pin "7") (pinfunction "HO_7") (pintype "input"))
    )
    (net (code "19") (name "Net-(D1_R1-A)") (class "Default")
      (node (ref "D1_R1") (pin "2") (pinfunction "A_2") (pintype "input"))
      (node (ref "Q1_R1") (pin "1") (pinfunction "G_1") (pintype "input"))
      (node (ref "R1_R1") (pin "2") (pinfunction "2_2") (pintype "input"))
    )
    (net (code "20") (name "Net-(D1_R1-C)") (class "Default")
      (node (ref "D1_R1") (pin "1") (pinfunction "C_1") (pintype "input"))
      (node (ref "R1_R1") (pin "1") (pinfunction "1_1") (pintype "input"))
      (node (ref "U1_R1") (pin "7") (pinfunction "HO_7") (pintype "input"))
    )
    (net (code "21") (name "Net-(D1_R2-A)") (class "Default")
      (node (ref "D1_R2") (pin "2") (pinfunction "A_2") (pintype "input"))
      (node (ref "Q1_R2") (pin "1") (pinfunction "G_1") (pintype "input"))
      (node (ref "R1_R2") (pin "2") (pinfunction "2_2") (pintype "input"))
    )
    (net (code "22") (name "Net-(D1_R2-C)") (class "Default")
      (node (ref "D1_R2") (pin "1") (pinfunction "C_1") (pintype "input"))
      (node (ref "R1_R2") (pin "1") (pinfunction "1_1") (pintype "input"))
      (node (ref "U1_R2") (pin "7") (pinfunction "HO_7") (pintype "input"))
    )
    (net (code "23") (name "Net-(D2_L1-A)") (class "Default")
      (node (ref "D2_L1") (pin "2") (pinfunction "A_2") (pintype "input"))
      (node (ref "Q2_L1") (pin "1") (pinfunction "G_1") (pintype "input"))
      (node (ref "R2_L1") (pin "2") (pinfunction "2_2") (pintype "input"))
    )
    (net (code "24") (name "Net-(D2_L1-C)") (class "Default")
      (node (ref "D2_L1") (pin "1") (pinfunction "C_1") (pintype "input"))
      (node (ref "R2_L1") (pin "1") (pinfunction "1_1") (pintype "input"))
      (node (ref "U1_L1") (pin "5") (pinfunction "LO_5") (pintype "input"))
    )
    (net (code "25") (name "Net-(D2_L2-A)") (class "Default")
      (node (ref "D2_L2") (pin "2") (pinfunction "A_2") (pintype "input"))
      (node (ref "Q2_L2") (pin "1") (pinfunction "G_1") (pintype "input"))
      (node (ref "R2_L2") (pin "2") (pinfunction "2_2") (pintype "input"))
    )
    (net (code "26") (name "Net-(D2_L2-C)") (class "Default")
      (node (ref "D2_L2") (pin "1") (pinfunction "C_1") (pintype "input"))
      (node (ref "R2_L2") (pin "1") (pinfunction "1_1") (pintype "input"))
      (node (ref "U1_L2") (pin "5") (pinfunction "LO_5") (pintype "input"))
    )
    (net (code "27") (name "Net-(D2_R1-A)") (class "Default")
      (node (ref "D2_R1") (pin "2") (pinfunction "A_2") (pintype "input"))
      (node (ref "Q2_R1") (pin "1") (pinfunction "G_1") (pintype "input"))
      (node (ref "R2_R1") (pin "2") (pinfunction "2_2") (pintype "input"))
    )
    (net (code "28") (name "Net-(D2_R1-C)") (class "Default")
      (node (ref "D2_R1") (pin "1") (pinfunction "C_1") (pintype "input"))
      (node (ref "R2_R1") (pin "1") (pinfunction "1_1") (pintype "input"))
      (node (ref "U1_R1") (pin "5") (pinfunction "LO_5") (pintype "input"))
    )
    (net (code "29") (name "Net-(D2_R2-A)") (class "Default")
      (node (ref "D2_R2") (pin "2") (pinfunction "A_2") (pintype "input"))
      (node (ref "Q2_R2") (pin "1") (pinfunction "G_1") (pintype "input"))
      (node (ref "R2_R2") (pin "2") (pinfunction "2_2") (pintype "input"))
    )
    (net (code "30") (name "Net-(D2_R2-C)") (class "Default")
      (node (ref "D2_R2") (pin "1") (pinfunction "C_1") (pintype "input"))
      (node (ref "R2_R2") (pin "1") (pinfunction "1_1") (pintype "input"))
      (node (ref "U1_R2") (pin "5") (pinfunction "LO_5") (pintype "input"))
    )
    (net (code "31") (name "Net-(D5_L1-K)") (class "Default")
      (node (ref "C2_L1") (pin "1") (pinfunction "1_1") (pintype "input"))
      (node (ref "D5_L1") (pin "1") (pinfunction "K_1") (pintype "input"))
      (node (ref "U1_L1") (pin "8") (pinfunction "VB_8") (pintype "input"))
    )
    (net (code "32") (name "Net-(D5_L2-K)") (class "Default")
      (node (ref "C2_L2") (pin "1") (pinfunction "1_1") (pintype "input"))
      (node (ref "D5_L2") (pin "1") (pinfunction "K_1") (pintype "input"))
      (node (ref "U1_L2") (pin "8") (pinfunction "VB_8") (pintype "input"))
    )
    (net (code "33") (name "Net-(D5_R1-K)") (class "Default")
      (node (ref "C2_R1") (pin "1") (pinfunction "1_1") (pintype "input"))
      (node (ref "D5_R1") (pin "1") (pinfunction "K_1") (pintype "input"))
      (node (ref "U1_R1") (pin "8") (pinfunction "VB_8") (pintype "input"))
    )
    (net (code "34") (name "Net-(D5_R2-K)") (class "Default")
      (node (ref "C2_R2") (pin "1") (pinfunction "1_1") (pintype "input"))
      (node (ref "D5_R2") (pin "1") (pinfunction "K_1") (pintype "input"))
      (node (ref "U1_R2") (pin "8") (pinfunction "VB_8") (pintype "input"))
    )
    (net (code "35") (name "Net-(LED1-A)") (class "Default")
      (node (ref "LED1") (pin "2") (pinfunction "A_2") (pintype "input"))
      (node (ref "R2") (pin "2") (pinfunction "2_2") (pintype "input"))
    )
    (net (code "36") (name "Net-(LED2-A)") (class "Default")
      (node (ref "LED2") (pin "2") (pinfunction "A_2") (pintype "input"))
      (node (ref "R3") (pin "1") (pinfunction "1_1") (pintype "input"))
    )
    (net (code "37") (name "Net-(LED3-A)") (class "Default")
      (node (ref "LED3") (pin "2") (pinfunction "A_2") (pintype "input"))
      (node (ref "R11") (pin "2") (pinfunction "2_2") (pintype "input"))
    )
    (net (code "38") (name "Net-(R4-Pad2)") (class "Default")
      (node (ref "R4") (pin "2") (pinfunction "2_2") (pintype "input"))
      (node (ref "R6") (pin "2") (pinfunction "2_2") (pintype "input"))
    )
    (net (code "39") (name "Net-(U3-FB)") (class "Default")
      (node (ref "R5") (pin "1") (pinfunction "1_1") (pintype "input"))
      (node (ref "R6") (pin "1") (pinfunction "1_1") (pintype "input"))
      (node (ref "U3") (pin "3") (pinfunction "FB_3") (pintype "input"))
    )
    (net (code "40") (name "Net-(U4-A1)") (class "Default")
      (node (ref "H1") (pin "5") (pinfunction "5_5") (pintype "input"))
      (node (ref "U4") (pin "2") (pinfunction "A1_2") (pintype "input"))
    )
    (net (code "41") (name "Net-(U4-A2)") (class "Default")
      (node (ref "H1") (pin "4") (pinfunction "4_4") (pintype "input"))
      (node (ref "U4") (pin "3") (pinfunction "A2_3") (pintype "input"))
    )
    (net (code "42") (name "Net-(U4-A3)") (class "Default")
      (node (ref "H1") (pin "3") (pinfunction "3_3") (pintype "input"))
      (node (ref "U4") (pin "4") (pinfunction "A3_4") (pintype "input"))
    )
    (net (code "43") (name "Net-(U4-A4)") (class "Default")
      (node (ref "H1") (pin "2") (pinfunction "2_2") (pintype "input"))
      (node (ref "U4") (pin "5") (pinfunction "A4_5") (pintype "input"))
    )
    (net (code "44") (name "PGND") (class "Default")
      (node (ref "C13") (pin "2") (pinfunction "2_2") (pintype "input"))
      (node (ref "CN1") (pin "1") (pinfunction "-_1") (pintype "input"))
      (node (ref "D4_L1") (pin "2") (pinfunction "A_2") (pintype "input"))
      (node (ref "D4_L2") (pin "2") (pinfunction "A_2") (pintype "input"))
      (node (ref "D4_R1") (pin "2") (pinfunction "A_2") (pintype "input"))
      (node (ref "D4_R2") (pin "2") (pinfunction "A_2") (pintype "input"))
      (node (ref "Q2_L1") (pin "3") (pinfunction "S_3") (pintype "input"))
      (node (ref "Q2_L2") (pin "3") (pinfunction "S_3") (pintype "input"))
      (node (ref "Q2_R1") (pin "3") (pinfunction "S_3") (pintype "input"))
      (node (ref "Q2_R2") (pin "3") (pinfunction "S_3") (pintype "input"))
      (node (ref "R12") (pin "1") (pinfunction "1_1") (pintype "input"))
    )
    (net (code "45") (name "VBAT") (class "Default")
      (node (ref "C1") (pin "2") (pinfunction "2_2") (pintype "input"))
      (node (ref "C10") (pin "2") (pinfunction "2_2") (pintype "input"))
      (node (ref "C2") (pin "2") (pinfunction "2_2") (pintype "input"))
      (node (ref "C9") (pin "2") (pinfunction "2_2") (pintype "input"))
      (node (ref "D3_L1") (pin "1") (pinfunction "C_1") (pintype "input"))
      (node (ref "D3_L2") (pin "1") (pinfunction "C_1") (pintype "input"))
      (node (ref "D3_R1") (pin "1") (pinfunction "C_1") (pintype "input"))
      (node (ref "D3_R2") (pin "1") (pinfunction "C_1") (pintype "input"))
      (node (ref "L1") (pin "2") (pinfunction "2_2") (pintype "input"))
      (node (ref "Q1_L1") (pin "2") (pinfunction "D_2") (pintype "input"))
      (node (ref "Q1_L2") (pin "2") (pinfunction "D_2") (pintype "input"))
      (node (ref "Q1_R1") (pin "2") (pinfunction "D_2") (pintype "input"))
      (node (ref "Q1_R2") (pin "2") (pinfunction "D_2") (pintype "input"))
      (node (ref "U2") (pin "3") (pinfunction "VIN_3") (pintype "input"))
      (node (ref "U3") (pin "4") (pinfunction "EN_4") (pintype "input"))
      (node (ref "U3") (pin "5") (pinfunction "VIN_5") (pintype "input"))
      (node (ref "U5") (pin "2") (pinfunction "2_2") (pintype "input"))
    )
    (net (code "46") (name "unconnected-(U1-VOUT(TAB)-Pad2)") (class "Default")
      (node (ref "U1") (pin "2") (pinfunction "VOUT(TAB)_2") (pintype "input+no_connect"))
    )
    (net (code "47") (name "unconnected-(U2-VOUT(TAB)-Pad2)") (class "Default")
      (node (ref "U2") (pin "2") (pinfunction "VOUT(TAB)_2") (pintype "input+no_connect"))
    )
    (net (code "48") (name "unconnected-(U3-NC-Pad6)") (class "Default")
      (node (ref "U3") (pin "6") (pinfunction "NC_6") (pintype "input+no_connect"))
    )
    (net (code "49") (name "unconnected-(U5-Pad3)") (class "Default")
      (node (ref "U5") (pin "3") (pinfunction "3_3") (pintype "input+no_connect"))
    )
  )
)
